# BTstackLE-Shield_v_1_0.net
KiCad netlist of a schematic drawn in EAGLE
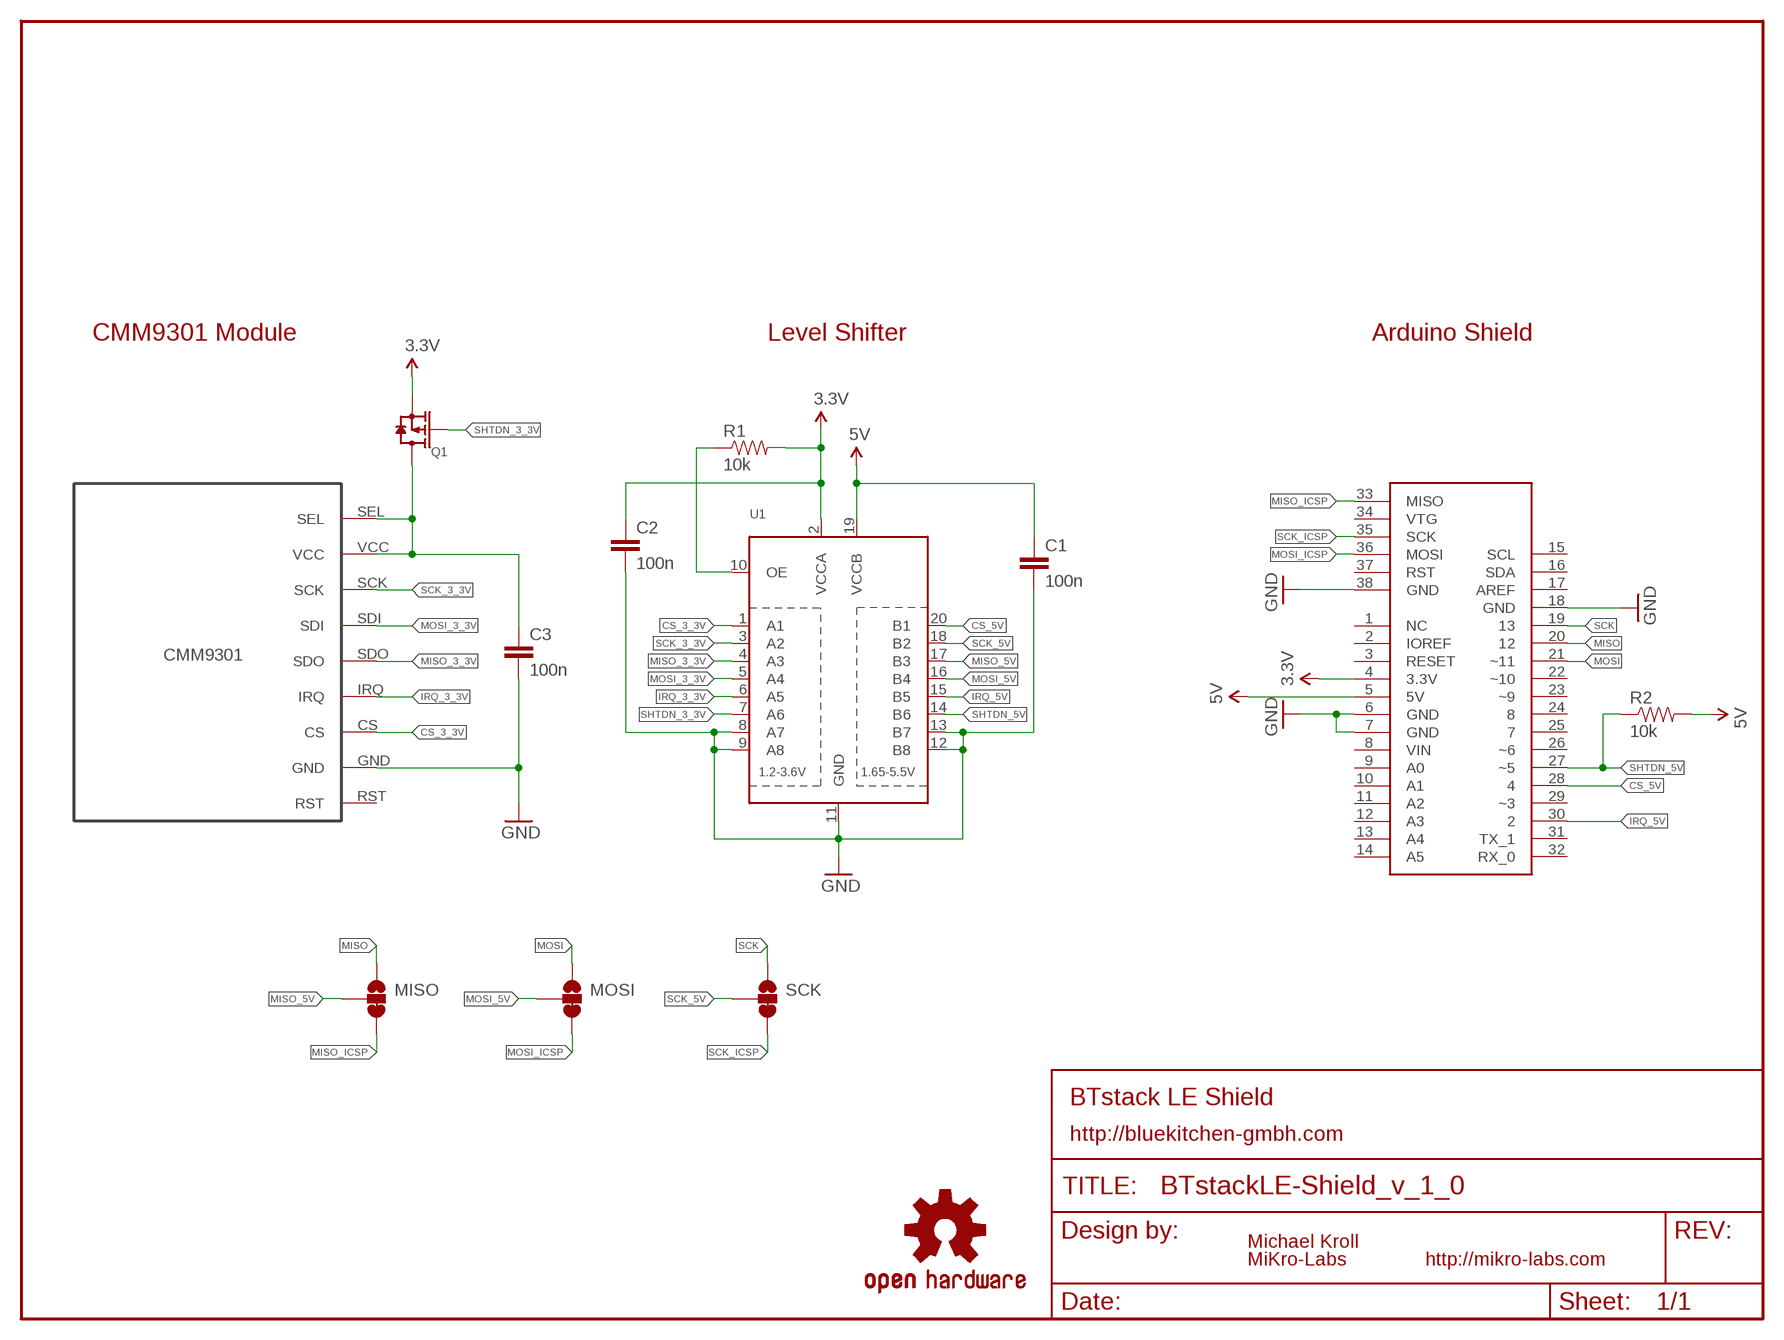
[diagram p0: schematic, sheet 1]

(export (version "E")
  (design (tool "Eeschema 10.0.6"))
  (components
    (comp (ref "C1")
      (value "100n")
      (footprint "eagle-import:0603-CAP")
      (libsource (lib "eagle-import") (part "CAP0603-CAP"))
    )
    (comp (ref "C2")
      (value "100n")
      (footprint "eagle-import:0603-CAP")
      (libsource (lib "eagle-import") (part "CAP0603-CAP"))
    )
    (comp (ref "C3")
      (value "100n")
      (footprint "eagle-import:0603-CAP")
      (libsource (lib "eagle-import") (part "CAP0603-CAP"))
    )
    (comp (ref "FRAME1")
      (value "FRAME-LETTER")
      (footprint "eagle-import:CREATIVE_COMMONS")
      (libsource (lib "eagle-import") (part "FRAME-LETTER"))
    )
    (comp (ref "LOGO1")
      (value "OSHW-LOGOL")
      (footprint "eagle-import:OSHW-LOGO-L")
      (libsource (lib "eagle-import") (part "OSHW-LOGOL"))
    )
    (comp (ref "MISO")
      (value "JUMPER-PAD-3-2OF3_NC_BY_TRACE_SMALL")
      (footprint "eagle-import:PAD-JUMPER-3-2OF3_NC_BY_TRACE_YES_SILK_FULL_BOX")
      (libsource (lib "eagle-import") (part "JUMPER-PAD-3-2OF3_NC_BY_TRACE_SMALL"))
    )
    (comp (ref "MOSI")
      (value "JUMPER-PAD-3-2OF3_NC_BY_TRACE_SMALL")
      (footprint "eagle-import:PAD-JUMPER-3-2OF3_NC_BY_TRACE_YES_SILK_FULL_BOX")
      (libsource (lib "eagle-import") (part "JUMPER-PAD-3-2OF3_NC_BY_TRACE_SMALL"))
    )
    (comp (ref "Q1")
      (value "MOSFET-P-0440210P1")
      (footprint "eagle-import:SOT23")
      (libsource (lib "eagle-import") (part "MOSFET-P-0440210P1"))
    )
    (comp (ref "R1")
      (value "10k")
      (footprint "eagle-import:0603-RES")
      (libsource (lib "eagle-import") (part "RESISTOR0603-RES"))
    )
    (comp (ref "R2")
      (value "10k")
      (footprint "eagle-import:0603-RES")
      (libsource (lib "eagle-import") (part "RESISTOR0603-RES"))
    )
    (comp (ref "SCK")
      (value "JUMPER-PAD-3-2OF3_NC_BY_TRACE_SMALL")
      (footprint "eagle-import:PAD-JUMPER-3-2OF3_NC_BY_TRACE_YES_SILK_FULL_BOX")
      (libsource (lib "eagle-import") (part "JUMPER-PAD-3-2OF3_NC_BY_TRACE_SMALL"))
    )
    (comp (ref "U$1")
      (value "ARDUINO_UNO_SHIELD_ICSP_PADS_ONLY")
      (footprint "eagle-import:ICSP_PADS_ONLY")
      (libsource (lib "eagle-import") (part "ARDUINO_UNO_SHIELD_ICSP_PADS_ONLY"))
    )
    (comp (ref "U$4")
      (value "CMM9301")
      (footprint "eagle-import:CMM9301")
      (libsource (lib "eagle-import") (part "CMM9301"))
    )
    (comp (ref "U1")
      (value "TXB0108PWR")
      (footprint "eagle-import:TSSOP20")
      (libsource (lib "eagle-import") (part "TXB0108PWR"))
    )
  )
  (nets
    (net (code "1") (name "3.3V") (class "Default")
      (node (ref "C2") (pin "1") (pinfunction "1_1") (pintype "passive"))
      (node (ref "Q1") (pin "2") (pinfunction "S_2") (pintype "passive"))
      (node (ref "R1") (pin "2") (pinfunction "2_2") (pintype "passive"))
      (node (ref "U$1") (pin "4") (pinfunction "3.3V_4") (pintype "bidirectional"))
      (node (ref "U1") (pin "2") (pinfunction "VCCA_2") (pintype "bidirectional"))
    )
    (net (code "2") (name "5V") (class "Default")
      (node (ref "C1") (pin "1") (pinfunction "1_1") (pintype "passive"))
      (node (ref "R2") (pin "2") (pinfunction "2_2") (pintype "passive"))
      (node (ref "U$1") (pin "5") (pinfunction "5V_5") (pintype "bidirectional"))
      (node (ref "U1") (pin "19") (pinfunction "VCCB_19") (pintype "bidirectional"))
    )
    (net (code "3") (name "CS_3_3V") (class "Default")
      (node (ref "U$4") (pin "CS") (pinfunction "CS_CS") (pintype "bidirectional"))
      (node (ref "U1") (pin "1") (pinfunction "A1_1") (pintype "bidirectional"))
    )
    (net (code "4") (name "CS_5V") (class "Default")
      (node (ref "U$1") (pin "28") (pinfunction "4_28") (pintype "bidirectional"))
      (node (ref "U1") (pin "20") (pinfunction "B1_20") (pintype "bidirectional"))
    )
    (net (code "5") (name "GND") (class "Default")
      (node (ref "C1") (pin "2") (pinfunction "2_2") (pintype "passive"))
      (node (ref "C2") (pin "2") (pinfunction "2_2") (pintype "passive"))
      (node (ref "C3") (pin "2") (pinfunction "2_2") (pintype "passive"))
      (node (ref "U$1") (pin "18") (pinfunction "GND_18") (pintype "bidirectional"))
      (node (ref "U$1") (pin "38") (pinfunction "GND_38") (pintype "bidirectional"))
      (node (ref "U$1") (pin "6") (pinfunction "GND_6") (pintype "bidirectional"))
      (node (ref "U$1") (pin "7") (pinfunction "GND_7") (pintype "bidirectional"))
      (node (ref "U$4") (pin "GND") (pinfunction "GND_GND") (pintype "power_in"))
      (node (ref "U1") (pin "11") (pinfunction "GND_11") (pintype "bidirectional"))
      (node (ref "U1") (pin "12") (pinfunction "B8_12") (pintype "bidirectional"))
      (node (ref "U1") (pin "13") (pinfunction "B7_13") (pintype "bidirectional"))
      (node (ref "U1") (pin "8") (pinfunction "A7_8") (pintype "bidirectional"))
      (node (ref "U1") (pin "9") (pinfunction "A8_9") (pintype "bidirectional"))
    )
    (net (code "6") (name "IRQ_3_3V") (class "Default")
      (node (ref "U$4") (pin "IRQ") (pinfunction "IRQ_IRQ") (pintype "bidirectional"))
      (node (ref "U1") (pin "6") (pinfunction "A5_6") (pintype "bidirectional"))
    )
    (net (code "7") (name "IRQ_5V") (class "Default")
      (node (ref "U$1") (pin "30") (pinfunction "2_30") (pintype "bidirectional"))
      (node (ref "U1") (pin "15") (pinfunction "B5_15") (pintype "bidirectional"))
    )
    (net (code "8") (name "MISO") (class "Default")
      (node (ref "MISO") (pin "1") (pinfunction "1_1") (pintype "passive"))
      (node (ref "U$1") (pin "20") (pinfunction "12_20") (pintype "bidirectional"))
    )
    (net (code "9") (name "MISO_3_3V") (class "Default")
      (node (ref "U$4") (pin "SDO") (pinfunction "SDO_SDO") (pintype "bidirectional"))
      (node (ref "U1") (pin "4") (pinfunction "A3_4") (pintype "bidirectional"))
    )
    (net (code "10") (name "MISO_5V") (class "Default")
      (node (ref "MISO") (pin "2") (pinfunction "2_2") (pintype "passive"))
      (node (ref "U1") (pin "17") (pinfunction "B3_17") (pintype "bidirectional"))
    )
    (net (code "11") (name "MISO_ICSP") (class "Default")
      (node (ref "MISO") (pin "3") (pinfunction "3_3") (pintype "passive"))
      (node (ref "U$1") (pin "33") (pinfunction "MISO_33") (pintype "bidirectional"))
    )
    (net (code "12") (name "MOSI") (class "Default")
      (node (ref "MOSI") (pin "1") (pinfunction "1_1") (pintype "passive"))
      (node (ref "U$1") (pin "21") (pinfunction "~{11}_21") (pintype "bidirectional"))
    )
    (net (code "13") (name "MOSI_3_3V") (class "Default")
      (node (ref "U$4") (pin "SDI") (pinfunction "SDI_SDI") (pintype "bidirectional"))
      (node (ref "U1") (pin "5") (pinfunction "A4_5") (pintype "bidirectional"))
    )
    (net (code "14") (name "MOSI_5V") (class "Default")
      (node (ref "MOSI") (pin "2") (pinfunction "2_2") (pintype "passive"))
      (node (ref "U1") (pin "16") (pinfunction "B4_16") (pintype "bidirectional"))
    )
    (net (code "15") (name "MOSI_ICSP") (class "Default")
      (node (ref "MOSI") (pin "3") (pinfunction "3_3") (pintype "passive"))
      (node (ref "U$1") (pin "36") (pinfunction "MOSI_36") (pintype "bidirectional"))
    )
    (net (code "16") (name "Net-(Q1-D)") (class "Default")
      (node (ref "C3") (pin "1") (pinfunction "1_1") (pintype "passive"))
      (node (ref "Q1") (pin "3") (pinfunction "D_3") (pintype "passive"))
      (node (ref "U$4") (pin "SEL") (pinfunction "SEL_SEL") (pintype "bidirectional"))
      (node (ref "U$4") (pin "VCC") (pinfunction "VCC_VCC") (pintype "power_in"))
    )
    (net (code "17") (name "Net-(U1-OE)") (class "Default")
      (node (ref "R1") (pin "1") (pinfunction "1_1") (pintype "passive"))
      (node (ref "U1") (pin "10") (pinfunction "OE_10") (pintype "bidirectional"))
    )
    (net (code "18") (name "SCK") (class "Default")
      (node (ref "SCK") (pin "1") (pinfunction "1_1") (pintype "passive"))
      (node (ref "U$1") (pin "19") (pinfunction "13_19") (pintype "bidirectional"))
    )
    (net (code "19") (name "SCK_3_3V") (class "Default")
      (node (ref "U$4") (pin "SCK") (pinfunction "SCK_SCK") (pintype "bidirectional"))
      (node (ref "U1") (pin "3") (pinfunction "A2_3") (pintype "bidirectional"))
    )
    (net (code "20") (name "SCK_5V") (class "Default")
      (node (ref "SCK") (pin "2") (pinfunction "2_2") (pintype "passive"))
      (node (ref "U1") (pin "18") (pinfunction "B2_18") (pintype "bidirectional"))
    )
    (net (code "21") (name "SCK_ICSP") (class "Default")
      (node (ref "SCK") (pin "3") (pinfunction "3_3") (pintype "passive"))
      (node (ref "U$1") (pin "35") (pinfunction "SCK_35") (pintype "bidirectional"))
    )
    (net (code "22") (name "SHTDN_3_3V") (class "Default")
      (node (ref "Q1") (pin "1") (pinfunction "G_1") (pintype "passive"))
      (node (ref "U1") (pin "7") (pinfunction "A6_7") (pintype "bidirectional"))
    )
    (net (code "23") (name "SHTDN_5V") (class "Default")
      (node (ref "R2") (pin "1") (pinfunction "1_1") (pintype "passive"))
      (node (ref "U$1") (pin "27") (pinfunction "~{5}_27") (pintype "bidirectional"))
      (node (ref "U1") (pin "14") (pinfunction "B6_14") (pintype "bidirectional"))
    )
    (net (code "24") (name "unconnected-(U$1-7-Pad25)") (class "Default")
      (node (ref "U$1") (pin "25") (pinfunction "7_25") (pintype "bidirectional"))
    )
    (net (code "25") (name "unconnected-(U$1-8-Pad24)") (class "Default")
      (node (ref "U$1") (pin "24") (pinfunction "8_24") (pintype "bidirectional"))
    )
    (net (code "26") (name "unconnected-(U$1-A0-Pad9)") (class "Default")
      (node (ref "U$1") (pin "9") (pinfunction "A0_9") (pintype "bidirectional"))
    )
    (net (code "27") (name "unconnected-(U$1-A1-Pad10)") (class "Default")
      (node (ref "U$1") (pin "10") (pinfunction "A1_10") (pintype "bidirectional"))
    )
    (net (code "28") (name "unconnected-(U$1-A2-Pad11)") (class "Default")
      (node (ref "U$1") (pin "11") (pinfunction "A2_11") (pintype "bidirectional"))
    )
    (net (code "29") (name "unconnected-(U$1-A3-Pad12)") (class "Default")
      (node (ref "U$1") (pin "12") (pinfunction "A3_12") (pintype "bidirectional"))
    )
    (net (code "30") (name "unconnected-(U$1-A4-Pad13)") (class "Default")
      (node (ref "U$1") (pin "13") (pinfunction "A4_13") (pintype "bidirectional"))
    )
    (net (code "31") (name "unconnected-(U$1-A5-Pad14)") (class "Default")
      (node (ref "U$1") (pin "14") (pinfunction "A5_14") (pintype "bidirectional"))
    )
    (net (code "32") (name "unconnected-(U$1-AREF-Pad17)") (class "Default")
      (node (ref "U$1") (pin "17") (pinfunction "AREF_17") (pintype "bidirectional"))
    )
    (net (code "33") (name "unconnected-(U$1-IOREF-Pad2)") (class "Default")
      (node (ref "U$1") (pin "2") (pinfunction "IOREF_2") (pintype "bidirectional"))
    )
    (net (code "34") (name "unconnected-(U$1-NC-Pad1)") (class "Default")
      (node (ref "U$1") (pin "1") (pinfunction "NC_1") (pintype "no_connect"))
    )
    (net (code "35") (name "unconnected-(U$1-RESET-Pad3)") (class "Default")
      (node (ref "U$1") (pin "3") (pinfunction "RESET_3") (pintype "bidirectional"))
    )
    (net (code "36") (name "unconnected-(U$1-RST-Pad37)") (class "Default")
      (node (ref "U$1") (pin "37") (pinfunction "RST_37") (pintype "bidirectional"))
    )
    (net (code "37") (name "unconnected-(U$1-RX_0-Pad32)") (class "Default")
      (node (ref "U$1") (pin "32") (pinfunction "RX_0_32") (pintype "bidirectional"))
    )
    (net (code "38") (name "unconnected-(U$1-SCL-Pad15)") (class "Default")
      (node (ref "U$1") (pin "15") (pinfunction "SCL_15") (pintype "bidirectional"))
    )
    (net (code "39") (name "unconnected-(U$1-SDA-Pad16)") (class "Default")
      (node (ref "U$1") (pin "16") (pinfunction "SDA_16") (pintype "bidirectional"))
    )
    (net (code "40") (name "unconnected-(U$1-TX_1-Pad31)") (class "Default")
      (node (ref "U$1") (pin "31") (pinfunction "TX_1_31") (pintype "bidirectional"))
    )
    (net (code "41") (name "unconnected-(U$1-VIN-Pad8)") (class "Default")
      (node (ref "U$1") (pin "8") (pinfunction "VIN_8") (pintype "bidirectional"))
    )
    (net (code "42") (name "unconnected-(U$1-VTG-Pad34)") (class "Default")
      (node (ref "U$1") (pin "34") (pinfunction "VTG_34") (pintype "bidirectional"))
    )
    (net (code "43") (name "unconnected-(U$1-~{3}-Pad29)") (class "Default")
      (node (ref "U$1") (pin "29") (pinfunction "~{3}_29") (pintype "bidirectional"))
    )
    (net (code "44") (name "unconnected-(U$1-~{6}-Pad26)") (class "Default")
      (node (ref "U$1") (pin "26") (pinfunction "~{6}_26") (pintype "bidirectional"))
    )
    (net (code "45") (name "unconnected-(U$1-~{9}-Pad23)") (class "Default")
      (node (ref "U$1") (pin "23") (pinfunction "~{9}_23") (pintype "bidirectional"))
    )
    (net (code "46") (name "unconnected-(U$1-~{10}-Pad22)") (class "Default")
      (node (ref "U$1") (pin "22") (pinfunction "~{10}_22") (pintype "bidirectional"))
    )
    (net (code "47") (name "unconnected-(U$4-PadRST)") (class "Default")
      (node (ref "U$4") (pin "RST") (pinfunction "RST_RST") (pintype "bidirectional"))
    )
  )
)
